# tgs2611-c00.net
KiCad netlist of a schematic drawn in EAGLE
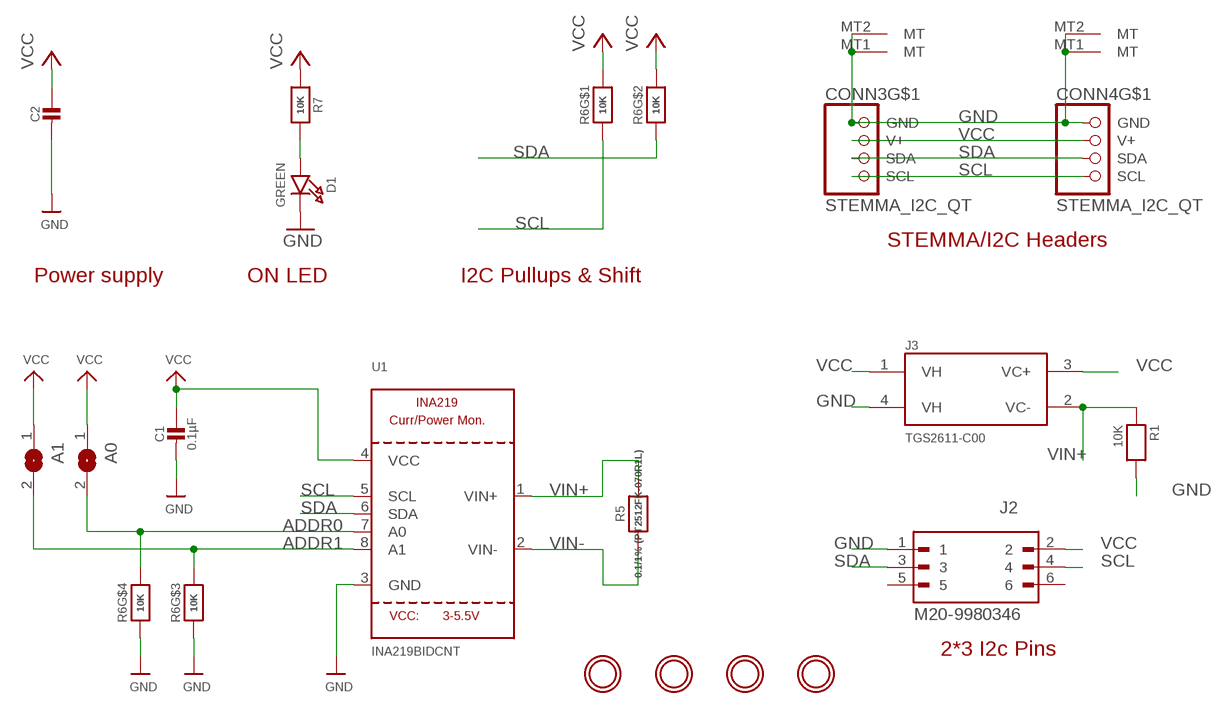
[diagram p0: schematic, sheet 1]

(export (version "E")
  (design (tool "Eeschema 10.0.6"))
  (components
    (comp (ref "A0")
      (value "SOLDERJUMPERREFLOW_NOPASTE")
      (footprint "eagle-import:SOLDERJUMPER_REFLOW_NOPASTE")
      (libsource (lib "eagle-import") (part "SOLDERJUMPERREFLOW_NOPASTE"))
    )
    (comp (ref "A1")
      (value "SOLDERJUMPERREFLOW_NOPASTE")
      (footprint "eagle-import:SOLDERJUMPER_REFLOW_NOPASTE")
      (libsource (lib "eagle-import") (part "SOLDERJUMPERREFLOW_NOPASTE"))
    )
    (comp (ref "C1")
      (value "0.1µF")
      (footprint "eagle-import:0603")
      (libsource (lib "eagle-import") (part "CAP_CERAMIC0603"))
    )
    (comp (ref "C2")
      (value "10uF")
      (footprint "eagle-import:_0805MP")
      (libsource (lib "eagle-import") (part "CAP_CERAMIC_0805MP"))
    )
    (comp (ref "CONN3")
      (value "STEMMA_I2C_QT")
      (footprint "eagle-import:JST_SH4")
      (libsource (lib "eagle-import") (part "STEMMA_I2C_QT"))
    )
    (comp (ref "CONN4")
      (value "STEMMA_I2C_QT")
      (footprint "eagle-import:JST_SH4")
      (libsource (lib "eagle-import") (part "STEMMA_I2C_QT"))
    )
    (comp (ref "D1")
      (value "GREEN")
      (footprint "eagle-import:CHIPLED_0603_NOOUTLINE")
      (libsource (lib "eagle-import") (part "LED0603_NOOUTLINE"))
    )
    (comp (ref "J2")
      (value "M20-9980346")
      (footprint "eagle-import:HARWIN_M20-9980346")
      (fields (field (name "MANUFACTURER") "HARWIN"))
      (libsource (lib "eagle-import") (part "M20-9980346"))
    )
    (comp (ref "J3")
      (value "TGS2611-C00")
      (footprint "eagle-import:TO180P920X780-4P")
      (fields (field (name "MF") "Figaro"))
      (libsource (lib "eagle-import") (part "TGS2611-C00"))
    )
    (comp (ref "R1")
      (value "10K")
      (footprint "eagle-import:0603")
      (libsource (lib "eagle-import") (part "RESISTOR0603"))
    )
    (comp (ref "R5")
      (value "0.1/1% (PT2512FK-070R1L)")
      (footprint "eagle-import:2512")
      (libsource (lib "eagle-import") (part "RESISTOR2512"))
    )
    (comp (ref "R6")
      (value "10K")
      (footprint "eagle-import:RESPACK_4X0603")
      (libsource (lib "eagle-import") (part "RESISTOR_4PACK"))
    )
    (comp (ref "R7")
      (value "10K")
      (footprint "eagle-import:_0603MP")
      (libsource (lib "eagle-import") (part "RESISTOR_0603MP"))
    )
    (comp (ref "U$1")
      (value "MOUNTINGHOLE2.5")
      (footprint "eagle-import:MOUNTINGHOLE_2.5_PLATED")
      (libsource (lib "eagle-import") (part "MOUNTINGHOLE2.5"))
    )
    (comp (ref "U$6")
      (value "MOUNTINGHOLE2.5")
      (footprint "eagle-import:MOUNTINGHOLE_2.5_PLATED")
      (libsource (lib "eagle-import") (part "MOUNTINGHOLE2.5"))
    )
    (comp (ref "U$7")
      (value "MOUNTINGHOLE2.5")
      (footprint "eagle-import:MOUNTINGHOLE_2.5_PLATED")
      (libsource (lib "eagle-import") (part "MOUNTINGHOLE2.5"))
    )
    (comp (ref "U$8")
      (value "MOUNTINGHOLE2.5")
      (footprint "eagle-import:MOUNTINGHOLE_2.5_PLATED")
      (libsource (lib "eagle-import") (part "MOUNTINGHOLE2.5"))
    )
    (comp (ref "U1")
      (value "INA219BIDCNT")
      (footprint "eagle-import:SOT23-8")
      (libsource (lib "eagle-import") (part "INA219"))
    )
  )
  (nets
    (net (code "1") (name "/ADDR0") (class "Default")
      (node (ref "A0") (pin "2") (pinfunction "2_2") (pintype "passive"))
      (node (ref "R6") (pin "5") (pinfunction "2_5") (pintype "passive"))
      (node (ref "U1") (pin "7") (pinfunction "A0_7") (pintype "bidirectional"))
    )
    (net (code "2") (name "/ADDR1") (class "Default")
      (node (ref "A1") (pin "2") (pinfunction "2_2") (pintype "passive"))
      (node (ref "R6") (pin "6") (pinfunction "2_6") (pintype "passive"))
      (node (ref "U1") (pin "8") (pinfunction "A1_8") (pintype "bidirectional"))
    )
    (net (code "3") (name "/SCL") (class "Default")
      (node (ref "CONN3") (pin "4") (pinfunction "SCL_4") (pintype "passive"))
      (node (ref "CONN4") (pin "4") (pinfunction "SCL_4") (pintype "passive"))
      (node (ref "J2") (pin "4") (pinfunction "4_4") (pintype "passive"))
      (node (ref "R6") (pin "1") (pinfunction "1_1") (pintype "passive"))
      (node (ref "U1") (pin "5") (pinfunction "SCL_5") (pintype "bidirectional"))
    )
    (net (code "4") (name "/SDA") (class "Default")
      (node (ref "CONN3") (pin "3") (pinfunction "SDA_3") (pintype "passive"))
      (node (ref "CONN4") (pin "3") (pinfunction "SDA_3") (pintype "passive"))
      (node (ref "J2") (pin "3") (pinfunction "3_3") (pintype "passive"))
      (node (ref "R6") (pin "2") (pinfunction "1_2") (pintype "passive"))
      (node (ref "U1") (pin "6") (pinfunction "SDA_6") (pintype "bidirectional"))
    )
    (net (code "5") (name "/VIN+") (class "Default")
      (node (ref "J3") (pin "2") (pinfunction "VC-_2") (pintype "power_in"))
      (node (ref "R1") (pin "1") (pinfunction "1_1") (pintype "passive"))
      (node (ref "R5") (pin "2") (pinfunction "2_2") (pintype "passive"))
      (node (ref "U1") (pin "1") (pinfunction "VIN+_1") (pintype "bidirectional"))
    )
    (net (code "6") (name "/VIN-") (class "Default")
      (node (ref "R5") (pin "1") (pinfunction "1_1") (pintype "passive"))
      (node (ref "U1") (pin "2") (pinfunction "VIN-_2") (pintype "bidirectional"))
    )
    (net (code "7") (name "GND") (class "Default")
      (node (ref "C1") (pin "2") (pinfunction "P$2_2") (pintype "passive"))
      (node (ref "C2") (pin "2") (pinfunction "P$2_2") (pintype "passive"))
      (node (ref "CONN3") (pin "1") (pinfunction "GND_1") (pintype "passive"))
      (node (ref "CONN3") (pin "MT1") (pinfunction "MT_MT1") (pintype "bidirectional"))
      (node (ref "CONN3") (pin "MT2") (pinfunction "MT_MT2") (pintype "bidirectional"))
      (node (ref "CONN4") (pin "1") (pinfunction "GND_1") (pintype "passive"))
      (node (ref "CONN4") (pin "MT1") (pinfunction "MT_MT1") (pintype "bidirectional"))
      (node (ref "CONN4") (pin "MT2") (pinfunction "MT_MT2") (pintype "bidirectional"))
      (node (ref "D1") (pin "C") (pinfunction "C_C") (pintype "passive"))
      (node (ref "J2") (pin "1") (pinfunction "1_1") (pintype "passive"))
      (node (ref "J3") (pin "4") (pinfunction "VH_4") (pintype "input"))
      (node (ref "R1") (pin "2") (pinfunction "2_2") (pintype "passive"))
      (node (ref "R6") (pin "3") (pinfunction "1_3") (pintype "passive"))
      (node (ref "R6") (pin "4") (pinfunction "1_4") (pintype "passive"))
      (node (ref "U1") (pin "3") (pinfunction "GND_3") (pintype "power_in"))
    )
    (net (code "8") (name "Net-(D1-PadA)") (class "Default")
      (node (ref "D1") (pin "A") (pinfunction "A_A") (pintype "passive"))
      (node (ref "R7") (pin "2") (pinfunction "2_2") (pintype "passive"))
    )
    (net (code "9") (name "VCC") (class "Default")
      (node (ref "A0") (pin "1") (pinfunction "1_1") (pintype "passive"))
      (node (ref "A1") (pin "1") (pinfunction "1_1") (pintype "passive"))
      (node (ref "C1") (pin "1") (pinfunction "P$1_1") (pintype "passive"))
      (node (ref "C2") (pin "1") (pinfunction "P$1_1") (pintype "passive"))
      (node (ref "CONN3") (pin "2") (pinfunction "V+_2") (pintype "passive"))
      (node (ref "CONN4") (pin "2") (pinfunction "V+_2") (pintype "passive"))
      (node (ref "J2") (pin "2") (pinfunction "2_2") (pintype "passive"))
      (node (ref "J3") (pin "1") (pinfunction "VH_1") (pintype "input"))
      (node (ref "J3") (pin "3") (pinfunction "VC+_3") (pintype "power_in"))
      (node (ref "R6") (pin "7") (pinfunction "2_7") (pintype "passive"))
      (node (ref "R6") (pin "8") (pinfunction "2_8") (pintype "passive"))
      (node (ref "R7") (pin "1") (pinfunction "1_1") (pintype "passive"))
      (node (ref "U1") (pin "4") (pinfunction "VCC_4") (pintype "power_in"))
    )
    (net (code "10") (name "unconnected-(J2-Pad5)") (class "Default")
      (node (ref "J2") (pin "5") (pinfunction "5_5") (pintype "passive"))
    )
    (net (code "11") (name "unconnected-(J2-Pad6)") (class "Default")
      (node (ref "J2") (pin "6") (pinfunction "6_6") (pintype "passive"))
    )
  )
)
